# Sheet_3.net
KiCad netlist of a schematic drawn in EasyEDA
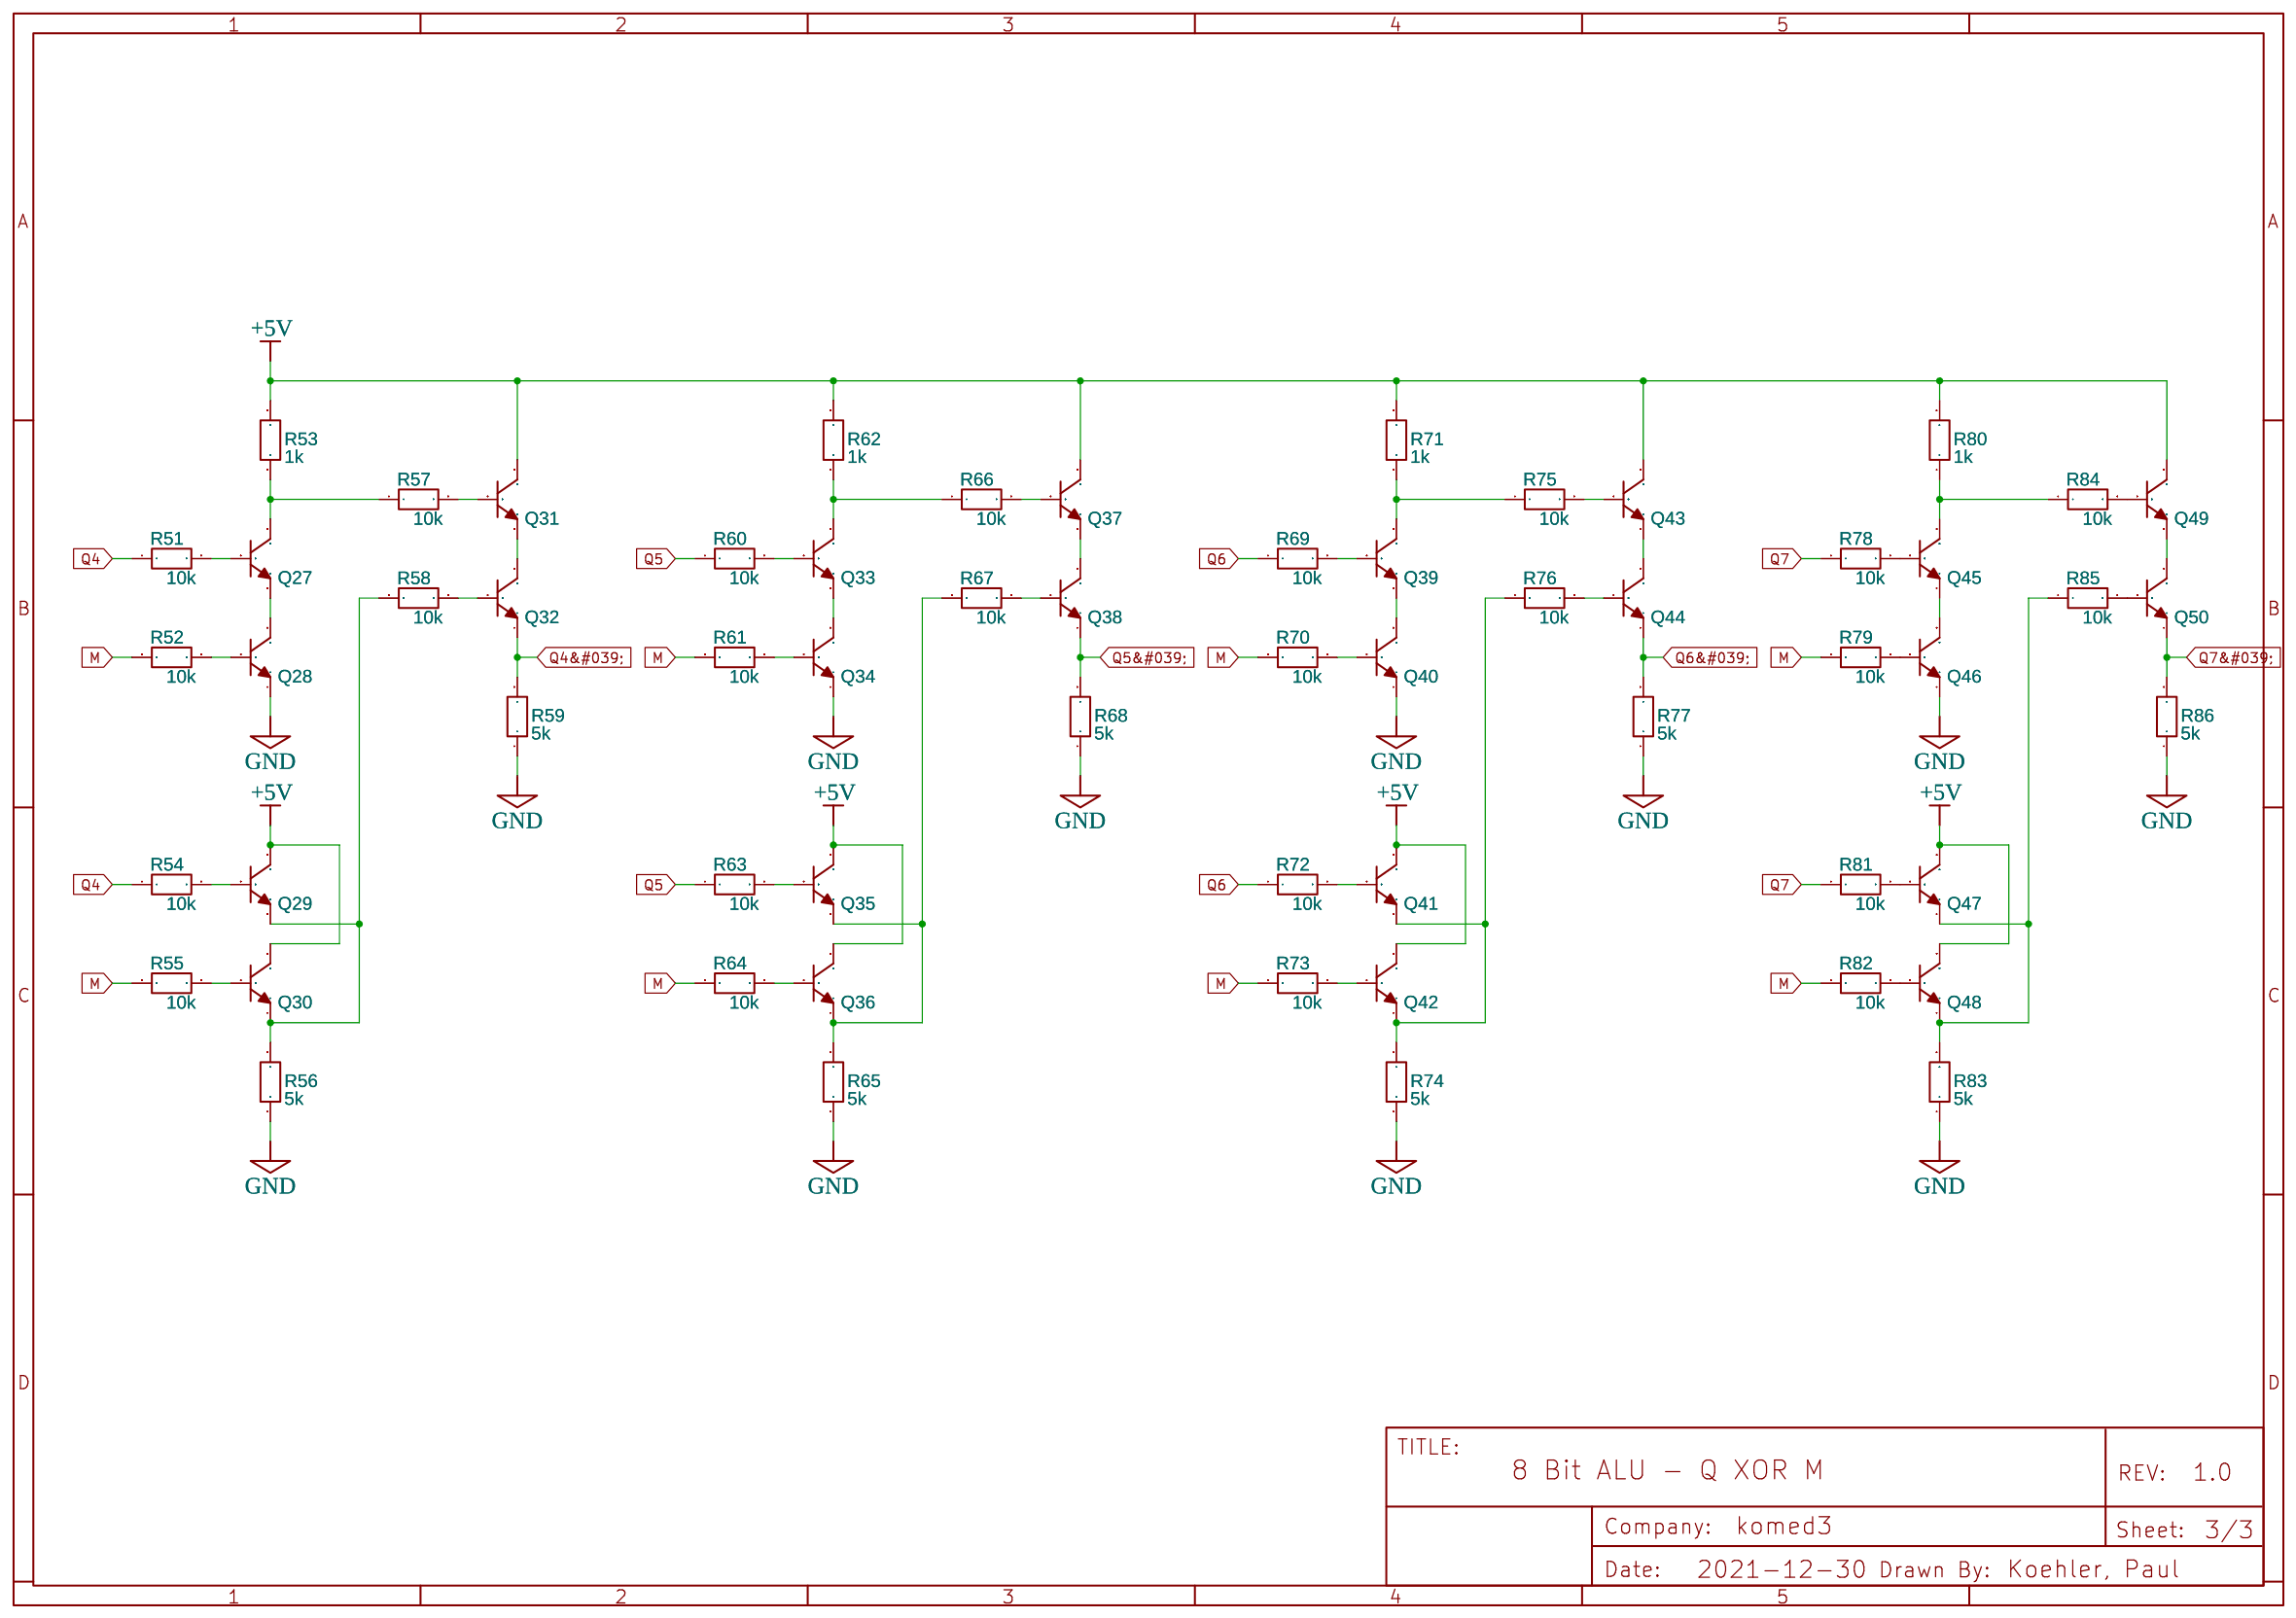
[diagram p0: schematic sheet]

(export (version "E")
  (design (tool "Eeschema 10.0.6"))
  (components
    (comp (ref "Q27")
      (value "2N3904(TO-92)")
      (fields (field (name "BOM_Manufacturer Part") "2N3904") (field (name "BOM_Supplier Part") "C118538"))
      (libsource (lib "") (part "2N3904(TO-92)"))
    )
    (comp (ref "Q28")
      (value "2N3904(TO-92)")
      (fields (field (name "BOM_Manufacturer Part") "2N3904") (field (name "BOM_Supplier Part") "C118538"))
      (libsource (lib "") (part "2N3904(TO-92)"))
    )
    (comp (ref "Q29")
      (value "2N3904(TO-92)")
      (fields (field (name "BOM_Manufacturer Part") "2N3904") (field (name "BOM_Supplier Part") "C118538"))
      (libsource (lib "") (part "2N3904(TO-92)"))
    )
    (comp (ref "Q30")
      (value "2N3904(TO-92)")
      (fields (field (name "BOM_Manufacturer Part") "2N3904") (field (name "BOM_Supplier Part") "C118538"))
      (libsource (lib "") (part "2N3904(TO-92)"))
    )
    (comp (ref "Q31")
      (value "2N3904(TO-92)")
      (fields (field (name "BOM_Manufacturer Part") "2N3904") (field (name "BOM_Supplier Part") "C118538"))
      (libsource (lib "") (part "2N3904(TO-92)"))
    )
    (comp (ref "Q32")
      (value "2N3904(TO-92)")
      (fields (field (name "BOM_Manufacturer Part") "2N3904") (field (name "BOM_Supplier Part") "C118538"))
      (libsource (lib "") (part "2N3904(TO-92)"))
    )
    (comp (ref "Q33")
      (value "2N3904(TO-92)")
      (fields (field (name "BOM_Manufacturer Part") "2N3904") (field (name "BOM_Supplier Part") "C118538"))
      (libsource (lib "") (part "2N3904(TO-92)"))
    )
    (comp (ref "Q34")
      (value "2N3904(TO-92)")
      (fields (field (name "BOM_Manufacturer Part") "2N3904") (field (name "BOM_Supplier Part") "C118538"))
      (libsource (lib "") (part "2N3904(TO-92)"))
    )
    (comp (ref "Q35")
      (value "2N3904(TO-92)")
      (fields (field (name "BOM_Manufacturer Part") "2N3904") (field (name "BOM_Supplier Part") "C118538"))
      (libsource (lib "") (part "2N3904(TO-92)"))
    )
    (comp (ref "Q36")
      (value "2N3904(TO-92)")
      (fields (field (name "BOM_Manufacturer Part") "2N3904") (field (name "BOM_Supplier Part") "C118538"))
      (libsource (lib "") (part "2N3904(TO-92)"))
    )
    (comp (ref "Q37")
      (value "2N3904(TO-92)")
      (fields (field (name "BOM_Manufacturer Part") "2N3904") (field (name "BOM_Supplier Part") "C118538"))
      (libsource (lib "") (part "2N3904(TO-92)"))
    )
    (comp (ref "Q38")
      (value "2N3904(TO-92)")
      (fields (field (name "BOM_Manufacturer Part") "2N3904") (field (name "BOM_Supplier Part") "C118538"))
      (libsource (lib "") (part "2N3904(TO-92)"))
    )
    (comp (ref "Q39")
      (value "2N3904(TO-92)")
      (fields (field (name "BOM_Manufacturer Part") "2N3904") (field (name "BOM_Supplier Part") "C118538"))
      (libsource (lib "") (part "2N3904(TO-92)"))
    )
    (comp (ref "Q40")
      (value "2N3904(TO-92)")
      (fields (field (name "BOM_Manufacturer Part") "2N3904") (field (name "BOM_Supplier Part") "C118538"))
      (libsource (lib "") (part "2N3904(TO-92)"))
    )
    (comp (ref "Q41")
      (value "2N3904(TO-92)")
      (fields (field (name "BOM_Manufacturer Part") "2N3904") (field (name "BOM_Supplier Part") "C118538"))
      (libsource (lib "") (part "2N3904(TO-92)"))
    )
    (comp (ref "Q42")
      (value "2N3904(TO-92)")
      (fields (field (name "BOM_Manufacturer Part") "2N3904") (field (name "BOM_Supplier Part") "C118538"))
      (libsource (lib "") (part "2N3904(TO-92)"))
    )
    (comp (ref "Q43")
      (value "2N3904(TO-92)")
      (fields (field (name "BOM_Manufacturer Part") "2N3904") (field (name "BOM_Supplier Part") "C118538"))
      (libsource (lib "") (part "2N3904(TO-92)"))
    )
    (comp (ref "Q44")
      (value "2N3904(TO-92)")
      (fields (field (name "BOM_Manufacturer Part") "2N3904") (field (name "BOM_Supplier Part") "C118538"))
      (libsource (lib "") (part "2N3904(TO-92)"))
    )
    (comp (ref "Q45")
      (value "2N3904(TO-92)")
      (fields (field (name "BOM_Manufacturer Part") "2N3904") (field (name "BOM_Supplier Part") "C118538"))
      (libsource (lib "") (part "2N3904(TO-92)"))
    )
    (comp (ref "Q46")
      (value "2N3904(TO-92)")
      (fields (field (name "BOM_Manufacturer Part") "2N3904") (field (name "BOM_Supplier Part") "C118538"))
      (libsource (lib "") (part "2N3904(TO-92)"))
    )
    (comp (ref "Q47")
      (value "2N3904(TO-92)")
      (fields (field (name "BOM_Manufacturer Part") "2N3904") (field (name "BOM_Supplier Part") "C118538"))
      (libsource (lib "") (part "2N3904(TO-92)"))
    )
    (comp (ref "Q48")
      (value "2N3904(TO-92)")
      (fields (field (name "BOM_Manufacturer Part") "2N3904") (field (name "BOM_Supplier Part") "C118538"))
      (libsource (lib "") (part "2N3904(TO-92)"))
    )
    (comp (ref "Q49")
      (value "2N3904(TO-92)")
      (fields (field (name "BOM_Manufacturer Part") "2N3904") (field (name "BOM_Supplier Part") "C118538"))
      (libsource (lib "") (part "2N3904(TO-92)"))
    )
    (comp (ref "Q50")
      (value "2N3904(TO-92)")
      (fields (field (name "BOM_Manufacturer Part") "2N3904") (field (name "BOM_Supplier Part") "C118538"))
      (libsource (lib "") (part "2N3904(TO-92)"))
    )
    (comp (ref "R51") (value "10k") (libsource (lib "") (part "R_AXIAL-0.3_EU")))
    (comp (ref "R52") (value "10k") (libsource (lib "") (part "R_AXIAL-0.3_EU")))
    (comp (ref "R53") (value "1k") (libsource (lib "") (part "R_AXIAL-0.3_EU_1")))
    (comp (ref "R54") (value "10k") (libsource (lib "") (part "R_AXIAL-0.3_EU")))
    (comp (ref "R55") (value "10k") (libsource (lib "") (part "R_AXIAL-0.3_EU")))
    (comp (ref "R56") (value "5k") (libsource (lib "") (part "R_AXIAL-0.3_EU_1")))
    (comp (ref "R57") (value "10k") (libsource (lib "") (part "R_AXIAL-0.3_EU")))
    (comp (ref "R58") (value "10k") (libsource (lib "") (part "R_AXIAL-0.3_EU")))
    (comp (ref "R59") (value "5k") (libsource (lib "") (part "R_AXIAL-0.3_EU_1")))
    (comp (ref "R60") (value "10k") (libsource (lib "") (part "R_AXIAL-0.3_EU")))
    (comp (ref "R61") (value "10k") (libsource (lib "") (part "R_AXIAL-0.3_EU")))
    (comp (ref "R62") (value "1k") (libsource (lib "") (part "R_AXIAL-0.3_EU_1")))
    (comp (ref "R63") (value "10k") (libsource (lib "") (part "R_AXIAL-0.3_EU")))
    (comp (ref "R64") (value "10k") (libsource (lib "") (part "R_AXIAL-0.3_EU")))
    (comp (ref "R65") (value "5k") (libsource (lib "") (part "R_AXIAL-0.3_EU_1")))
    (comp (ref "R66") (value "10k") (libsource (lib "") (part "R_AXIAL-0.3_EU")))
    (comp (ref "R67") (value "10k") (libsource (lib "") (part "R_AXIAL-0.3_EU")))
    (comp (ref "R68") (value "5k") (libsource (lib "") (part "R_AXIAL-0.3_EU_1")))
    (comp (ref "R69") (value "10k") (libsource (lib "") (part "R_AXIAL-0.3_EU")))
    (comp (ref "R70") (value "10k") (libsource (lib "") (part "R_AXIAL-0.3_EU")))
    (comp (ref "R71") (value "1k") (libsource (lib "") (part "R_AXIAL-0.3_EU_1")))
    (comp (ref "R72") (value "10k") (libsource (lib "") (part "R_AXIAL-0.3_EU")))
    (comp (ref "R73") (value "10k") (libsource (lib "") (part "R_AXIAL-0.3_EU")))
    (comp (ref "R74") (value "5k") (libsource (lib "") (part "R_AXIAL-0.3_EU_1")))
    (comp (ref "R75") (value "10k") (libsource (lib "") (part "R_AXIAL-0.3_EU")))
    (comp (ref "R76") (value "10k") (libsource (lib "") (part "R_AXIAL-0.3_EU")))
    (comp (ref "R77") (value "5k") (libsource (lib "") (part "R_AXIAL-0.3_EU_1")))
    (comp (ref "R78") (value "10k") (libsource (lib "") (part "R_AXIAL-0.3_EU")))
    (comp (ref "R79") (value "10k") (libsource (lib "") (part "R_AXIAL-0.3_EU")))
    (comp (ref "R80") (value "1k") (libsource (lib "") (part "R_AXIAL-0.3_EU_1")))
    (comp (ref "R81") (value "10k") (libsource (lib "") (part "R_AXIAL-0.3_EU")))
    (comp (ref "R82") (value "10k") (libsource (lib "") (part "R_AXIAL-0.3_EU")))
    (comp (ref "R83") (value "5k") (libsource (lib "") (part "R_AXIAL-0.3_EU_1")))
    (comp (ref "R84") (value "10k") (libsource (lib "") (part "R_AXIAL-0.3_EU")))
    (comp (ref "R85") (value "10k") (libsource (lib "") (part "R_AXIAL-0.3_EU")))
    (comp (ref "R86") (value "5k") (libsource (lib "") (part "R_AXIAL-0.3_EU_1")))
  )
  (nets
    (net (code "1") (name "+5V") (class "Default")
      (node (ref "Q29") (pin "3") (pinfunction "C_3") (pintype "unspecified"))
      (node (ref "Q30") (pin "3") (pinfunction "C_3") (pintype "unspecified"))
      (node (ref "Q31") (pin "3") (pinfunction "C_3") (pintype "unspecified"))
      (node (ref "Q35") (pin "3") (pinfunction "C_3") (pintype "unspecified"))
      (node (ref "Q36") (pin "3") (pinfunction "C_3") (pintype "unspecified"))
      (node (ref "Q37") (pin "3") (pinfunction "C_3") (pintype "unspecified"))
      (node (ref "Q41") (pin "3") (pinfunction "C_3") (pintype "unspecified"))
      (node (ref "Q42") (pin "3") (pinfunction "C_3") (pintype "unspecified"))
      (node (ref "Q43") (pin "3") (pinfunction "C_3") (pintype "unspecified"))
      (node (ref "Q47") (pin "3") (pinfunction "C_3") (pintype "unspecified"))
      (node (ref "Q48") (pin "3") (pinfunction "C_3") (pintype "unspecified"))
      (node (ref "Q49") (pin "3") (pinfunction "C_3") (pintype "unspecified"))
      (node (ref "R53") (pin "2") (pinfunction "2_2") (pintype "unspecified"))
      (node (ref "R62") (pin "2") (pinfunction "2_2") (pintype "unspecified"))
      (node (ref "R71") (pin "2") (pinfunction "2_2") (pintype "unspecified"))
      (node (ref "R80") (pin "2") (pinfunction "2_2") (pintype "unspecified"))
    )
    (net (code "2") (name "GND") (class "Default")
      (node (ref "Q28") (pin "1") (pinfunction "E_1") (pintype "unspecified"))
      (node (ref "Q34") (pin "1") (pinfunction "E_1") (pintype "unspecified"))
      (node (ref "Q40") (pin "1") (pinfunction "E_1") (pintype "unspecified"))
      (node (ref "Q46") (pin "1") (pinfunction "E_1") (pintype "unspecified"))
      (node (ref "R56") (pin "1") (pinfunction "1_1") (pintype "unspecified"))
      (node (ref "R59") (pin "1") (pinfunction "1_1") (pintype "unspecified"))
      (node (ref "R65") (pin "1") (pinfunction "1_1") (pintype "unspecified"))
      (node (ref "R68") (pin "1") (pinfunction "1_1") (pintype "unspecified"))
      (node (ref "R74") (pin "1") (pinfunction "1_1") (pintype "unspecified"))
      (node (ref "R77") (pin "1") (pinfunction "1_1") (pintype "unspecified"))
      (node (ref "R83") (pin "1") (pinfunction "1_1") (pintype "unspecified"))
      (node (ref "R86") (pin "1") (pinfunction "1_1") (pintype "unspecified"))
    )
    (net (code "3") (name "M") (class "Default")
      (node (ref "R52") (pin "1") (pinfunction "1_1") (pintype "unspecified"))
      (node (ref "R55") (pin "1") (pinfunction "1_1") (pintype "unspecified"))
      (node (ref "R61") (pin "1") (pinfunction "1_1") (pintype "unspecified"))
      (node (ref "R64") (pin "1") (pinfunction "1_1") (pintype "unspecified"))
      (node (ref "R70") (pin "1") (pinfunction "1_1") (pintype "unspecified"))
      (node (ref "R73") (pin "1") (pinfunction "1_1") (pintype "unspecified"))
      (node (ref "R79") (pin "1") (pinfunction "1_1") (pintype "unspecified"))
      (node (ref "R82") (pin "1") (pinfunction "1_1") (pintype "unspecified"))
    )
    (net (code "4") (name "Net-(Q27-B)") (class "Default")
      (node (ref "Q27") (pin "2") (pinfunction "B_2") (pintype "unspecified"))
      (node (ref "R51") (pin "2") (pinfunction "2_2") (pintype "unspecified"))
    )
    (net (code "5") (name "Net-(Q27-C)") (class "Default")
      (node (ref "Q27") (pin "3") (pinfunction "C_3") (pintype "unspecified"))
      (node (ref "R53") (pin "1") (pinfunction "1_1") (pintype "unspecified"))
      (node (ref "R57") (pin "1") (pinfunction "1_1") (pintype "unspecified"))
    )
    (net (code "6") (name "Net-(Q27-E)") (class "Default")
      (node (ref "Q27") (pin "1") (pinfunction "E_1") (pintype "unspecified"))
      (node (ref "Q28") (pin "3") (pinfunction "C_3") (pintype "unspecified"))
    )
    (net (code "7") (name "Net-(Q28-B)") (class "Default")
      (node (ref "Q28") (pin "2") (pinfunction "B_2") (pintype "unspecified"))
      (node (ref "R52") (pin "2") (pinfunction "2_2") (pintype "unspecified"))
    )
    (net (code "8") (name "Net-(Q29-B)") (class "Default")
      (node (ref "Q29") (pin "2") (pinfunction "B_2") (pintype "unspecified"))
      (node (ref "R54") (pin "2") (pinfunction "2_2") (pintype "unspecified"))
    )
    (net (code "9") (name "Net-(Q29-E)") (class "Default")
      (node (ref "Q29") (pin "1") (pinfunction "E_1") (pintype "unspecified"))
      (node (ref "Q30") (pin "1") (pinfunction "E_1") (pintype "unspecified"))
      (node (ref "R56") (pin "2") (pinfunction "2_2") (pintype "unspecified"))
      (node (ref "R58") (pin "1") (pinfunction "1_1") (pintype "unspecified"))
    )
    (net (code "10") (name "Net-(Q30-B)") (class "Default")
      (node (ref "Q30") (pin "2") (pinfunction "B_2") (pintype "unspecified"))
      (node (ref "R55") (pin "2") (pinfunction "2_2") (pintype "unspecified"))
    )
    (net (code "11") (name "Net-(Q31-B)") (class "Default")
      (node (ref "Q31") (pin "2") (pinfunction "B_2") (pintype "unspecified"))
      (node (ref "R57") (pin "2") (pinfunction "2_2") (pintype "unspecified"))
    )
    (net (code "12") (name "Net-(Q31-E)") (class "Default")
      (node (ref "Q31") (pin "1") (pinfunction "E_1") (pintype "unspecified"))
      (node (ref "Q32") (pin "3") (pinfunction "C_3") (pintype "unspecified"))
    )
    (net (code "13") (name "Net-(Q32-B)") (class "Default")
      (node (ref "Q32") (pin "2") (pinfunction "B_2") (pintype "unspecified"))
      (node (ref "R58") (pin "2") (pinfunction "2_2") (pintype "unspecified"))
    )
    (net (code "14") (name "Net-(Q33-B)") (class "Default")
      (node (ref "Q33") (pin "2") (pinfunction "B_2") (pintype "unspecified"))
      (node (ref "R60") (pin "2") (pinfunction "2_2") (pintype "unspecified"))
    )
    (net (code "15") (name "Net-(Q33-C)") (class "Default")
      (node (ref "Q33") (pin "3") (pinfunction "C_3") (pintype "unspecified"))
      (node (ref "R62") (pin "1") (pinfunction "1_1") (pintype "unspecified"))
      (node (ref "R66") (pin "1") (pinfunction "1_1") (pintype "unspecified"))
    )
    (net (code "16") (name "Net-(Q33-E)") (class "Default")
      (node (ref "Q33") (pin "1") (pinfunction "E_1") (pintype "unspecified"))
      (node (ref "Q34") (pin "3") (pinfunction "C_3") (pintype "unspecified"))
    )
    (net (code "17") (name "Net-(Q34-B)") (class "Default")
      (node (ref "Q34") (pin "2") (pinfunction "B_2") (pintype "unspecified"))
      (node (ref "R61") (pin "2") (pinfunction "2_2") (pintype "unspecified"))
    )
    (net (code "18") (name "Net-(Q35-B)") (class "Default")
      (node (ref "Q35") (pin "2") (pinfunction "B_2") (pintype "unspecified"))
      (node (ref "R63") (pin "2") (pinfunction "2_2") (pintype "unspecified"))
    )
    (net (code "19") (name "Net-(Q35-E)") (class "Default")
      (node (ref "Q35") (pin "1") (pinfunction "E_1") (pintype "unspecified"))
      (node (ref "Q36") (pin "1") (pinfunction "E_1") (pintype "unspecified"))
      (node (ref "R65") (pin "2") (pinfunction "2_2") (pintype "unspecified"))
      (node (ref "R67") (pin "1") (pinfunction "1_1") (pintype "unspecified"))
    )
    (net (code "20") (name "Net-(Q36-B)") (class "Default")
      (node (ref "Q36") (pin "2") (pinfunction "B_2") (pintype "unspecified"))
      (node (ref "R64") (pin "2") (pinfunction "2_2") (pintype "unspecified"))
    )
    (net (code "21") (name "Net-(Q37-B)") (class "Default")
      (node (ref "Q37") (pin "2") (pinfunction "B_2") (pintype "unspecified"))
      (node (ref "R66") (pin "2") (pinfunction "2_2") (pintype "unspecified"))
    )
    (net (code "22") (name "Net-(Q37-E)") (class "Default")
      (node (ref "Q37") (pin "1") (pinfunction "E_1") (pintype "unspecified"))
      (node (ref "Q38") (pin "3") (pinfunction "C_3") (pintype "unspecified"))
    )
    (net (code "23") (name "Net-(Q38-B)") (class "Default")
      (node (ref "Q38") (pin "2") (pinfunction "B_2") (pintype "unspecified"))
      (node (ref "R67") (pin "2") (pinfunction "2_2") (pintype "unspecified"))
    )
    (net (code "24") (name "Net-(Q39-B)") (class "Default")
      (node (ref "Q39") (pin "2") (pinfunction "B_2") (pintype "unspecified"))
      (node (ref "R69") (pin "2") (pinfunction "2_2") (pintype "unspecified"))
    )
    (net (code "25") (name "Net-(Q39-C)") (class "Default")
      (node (ref "Q39") (pin "3") (pinfunction "C_3") (pintype "unspecified"))
      (node (ref "R71") (pin "1") (pinfunction "1_1") (pintype "unspecified"))
      (node (ref "R75") (pin "1") (pinfunction "1_1") (pintype "unspecified"))
    )
    (net (code "26") (name "Net-(Q39-E)") (class "Default")
      (node (ref "Q39") (pin "1") (pinfunction "E_1") (pintype "unspecified"))
      (node (ref "Q40") (pin "3") (pinfunction "C_3") (pintype "unspecified"))
    )
    (net (code "27") (name "Net-(Q40-B)") (class "Default")
      (node (ref "Q40") (pin "2") (pinfunction "B_2") (pintype "unspecified"))
      (node (ref "R70") (pin "2") (pinfunction "2_2") (pintype "unspecified"))
    )
    (net (code "28") (name "Net-(Q41-B)") (class "Default")
      (node (ref "Q41") (pin "2") (pinfunction "B_2") (pintype "unspecified"))
      (node (ref "R72") (pin "2") (pinfunction "2_2") (pintype "unspecified"))
    )
    (net (code "29") (name "Net-(Q41-E)") (class "Default")
      (node (ref "Q41") (pin "1") (pinfunction "E_1") (pintype "unspecified"))
      (node (ref "Q42") (pin "1") (pinfunction "E_1") (pintype "unspecified"))
      (node (ref "R74") (pin "2") (pinfunction "2_2") (pintype "unspecified"))
      (node (ref "R76") (pin "1") (pinfunction "1_1") (pintype "unspecified"))
    )
    (net (code "30") (name "Net-(Q42-B)") (class "Default")
      (node (ref "Q42") (pin "2") (pinfunction "B_2") (pintype "unspecified"))
      (node (ref "R73") (pin "2") (pinfunction "2_2") (pintype "unspecified"))
    )
    (net (code "31") (name "Net-(Q43-B)") (class "Default")
      (node (ref "Q43") (pin "2") (pinfunction "B_2") (pintype "unspecified"))
      (node (ref "R75") (pin "2") (pinfunction "2_2") (pintype "unspecified"))
    )
    (net (code "32") (name "Net-(Q43-E)") (class "Default")
      (node (ref "Q43") (pin "1") (pinfunction "E_1") (pintype "unspecified"))
      (node (ref "Q44") (pin "3") (pinfunction "C_3") (pintype "unspecified"))
    )
    (net (code "33") (name "Net-(Q44-B)") (class "Default")
      (node (ref "Q44") (pin "2") (pinfunction "B_2") (pintype "unspecified"))
      (node (ref "R76") (pin "2") (pinfunction "2_2") (pintype "unspecified"))
    )
    (net (code "34") (name "Net-(Q45-B)") (class "Default")
      (node (ref "Q45") (pin "2") (pinfunction "B_2") (pintype "unspecified"))
      (node (ref "R78") (pin "2") (pinfunction "2_2") (pintype "unspecified"))
    )
    (net (code "35") (name "Net-(Q45-C)") (class "Default")
      (node (ref "Q45") (pin "3") (pinfunction "C_3") (pintype "unspecified"))
      (node (ref "R80") (pin "1") (pinfunction "1_1") (pintype "unspecified"))
      (node (ref "R84") (pin "1") (pinfunction "1_1") (pintype "unspecified"))
    )
    (net (code "36") (name "Net-(Q45-E)") (class "Default")
      (node (ref "Q45") (pin "1") (pinfunction "E_1") (pintype "unspecified"))
      (node (ref "Q46") (pin "3") (pinfunction "C_3") (pintype "unspecified"))
    )
    (net (code "37") (name "Net-(Q46-B)") (class "Default")
      (node (ref "Q46") (pin "2") (pinfunction "B_2") (pintype "unspecified"))
      (node (ref "R79") (pin "2") (pinfunction "2_2") (pintype "unspecified"))
    )
    (net (code "38") (name "Net-(Q47-B)") (class "Default")
      (node (ref "Q47") (pin "2") (pinfunction "B_2") (pintype "unspecified"))
      (node (ref "R81") (pin "2") (pinfunction "2_2") (pintype "unspecified"))
    )
    (net (code "39") (name "Net-(Q47-E)") (class "Default")
      (node (ref "Q47") (pin "1") (pinfunction "E_1") (pintype "unspecified"))
      (node (ref "Q48") (pin "1") (pinfunction "E_1") (pintype "unspecified"))
      (node (ref "R83") (pin "2") (pinfunction "2_2") (pintype "unspecified"))
      (node (ref "R85") (pin "1") (pinfunction "1_1") (pintype "unspecified"))
    )
    (net (code "40") (name "Net-(Q48-B)") (class "Default")
      (node (ref "Q48") (pin "2") (pinfunction "B_2") (pintype "unspecified"))
      (node (ref "R82") (pin "2") (pinfunction "2_2") (pintype "unspecified"))
    )
    (net (code "41") (name "Net-(Q49-B)") (class "Default")
      (node (ref "Q49") (pin "2") (pinfunction "B_2") (pintype "unspecified"))
      (node (ref "R84") (pin "2") (pinfunction "2_2") (pintype "unspecified"))
    )
    (net (code "42") (name "Net-(Q49-E)") (class "Default")
      (node (ref "Q49") (pin "1") (pinfunction "E_1") (pintype "unspecified"))
      (node (ref "Q50") (pin "3") (pinfunction "C_3") (pintype "unspecified"))
    )
    (net (code "43") (name "Net-(Q50-B)") (class "Default")
      (node (ref "Q50") (pin "2") (pinfunction "B_2") (pintype "unspecified"))
      (node (ref "R85") (pin "2") (pinfunction "2_2") (pintype "unspecified"))
    )
    (net (code "44") (name "Q4") (class "Default")
      (node (ref "R51") (pin "1") (pinfunction "1_1") (pintype "unspecified"))
      (node (ref "R54") (pin "1") (pinfunction "1_1") (pintype "unspecified"))
    )
    (net (code "45") (name "Q4&#039;") (class "Default")
      (node (ref "Q32") (pin "1") (pinfunction "E_1") (pintype "unspecified"))
      (node (ref "R59") (pin "2") (pinfunction "2_2") (pintype "unspecified"))
    )
    (net (code "46") (name "Q5") (class "Default")
      (node (ref "R60") (pin "1") (pinfunction "1_1") (pintype "unspecified"))
      (node (ref "R63") (pin "1") (pinfunction "1_1") (pintype "unspecified"))
    )
    (net (code "47") (name "Q5&#039;") (class "Default")
      (node (ref "Q38") (pin "1") (pinfunction "E_1") (pintype "unspecified"))
      (node (ref "R68") (pin "2") (pinfunction "2_2") (pintype "unspecified"))
    )
    (net (code "48") (name "Q6") (class "Default")
      (node (ref "R69") (pin "1") (pinfunction "1_1") (pintype "unspecified"))
      (node (ref "R72") (pin "1") (pinfunction "1_1") (pintype "unspecified"))
    )
    (net (code "49") (name "Q6&#039;") (class "Default")
      (node (ref "Q44") (pin "1") (pinfunction "E_1") (pintype "unspecified"))
      (node (ref "R77") (pin "2") (pinfunction "2_2") (pintype "unspecified"))
    )
    (net (code "50") (name "Q7") (class "Default")
      (node (ref "R78") (pin "1") (pinfunction "1_1") (pintype "unspecified"))
      (node (ref "R81") (pin "1") (pinfunction "1_1") (pintype "unspecified"))
    )
    (net (code "51") (name "Q7&#039;") (class "Default")
      (node (ref "Q50") (pin "1") (pinfunction "E_1") (pintype "unspecified"))
      (node (ref "R86") (pin "2") (pinfunction "2_2") (pintype "unspecified"))
    )
  )
)
